# STM32_Schematic.net
KiCad netlist of a schematic drawn in Altium Designer
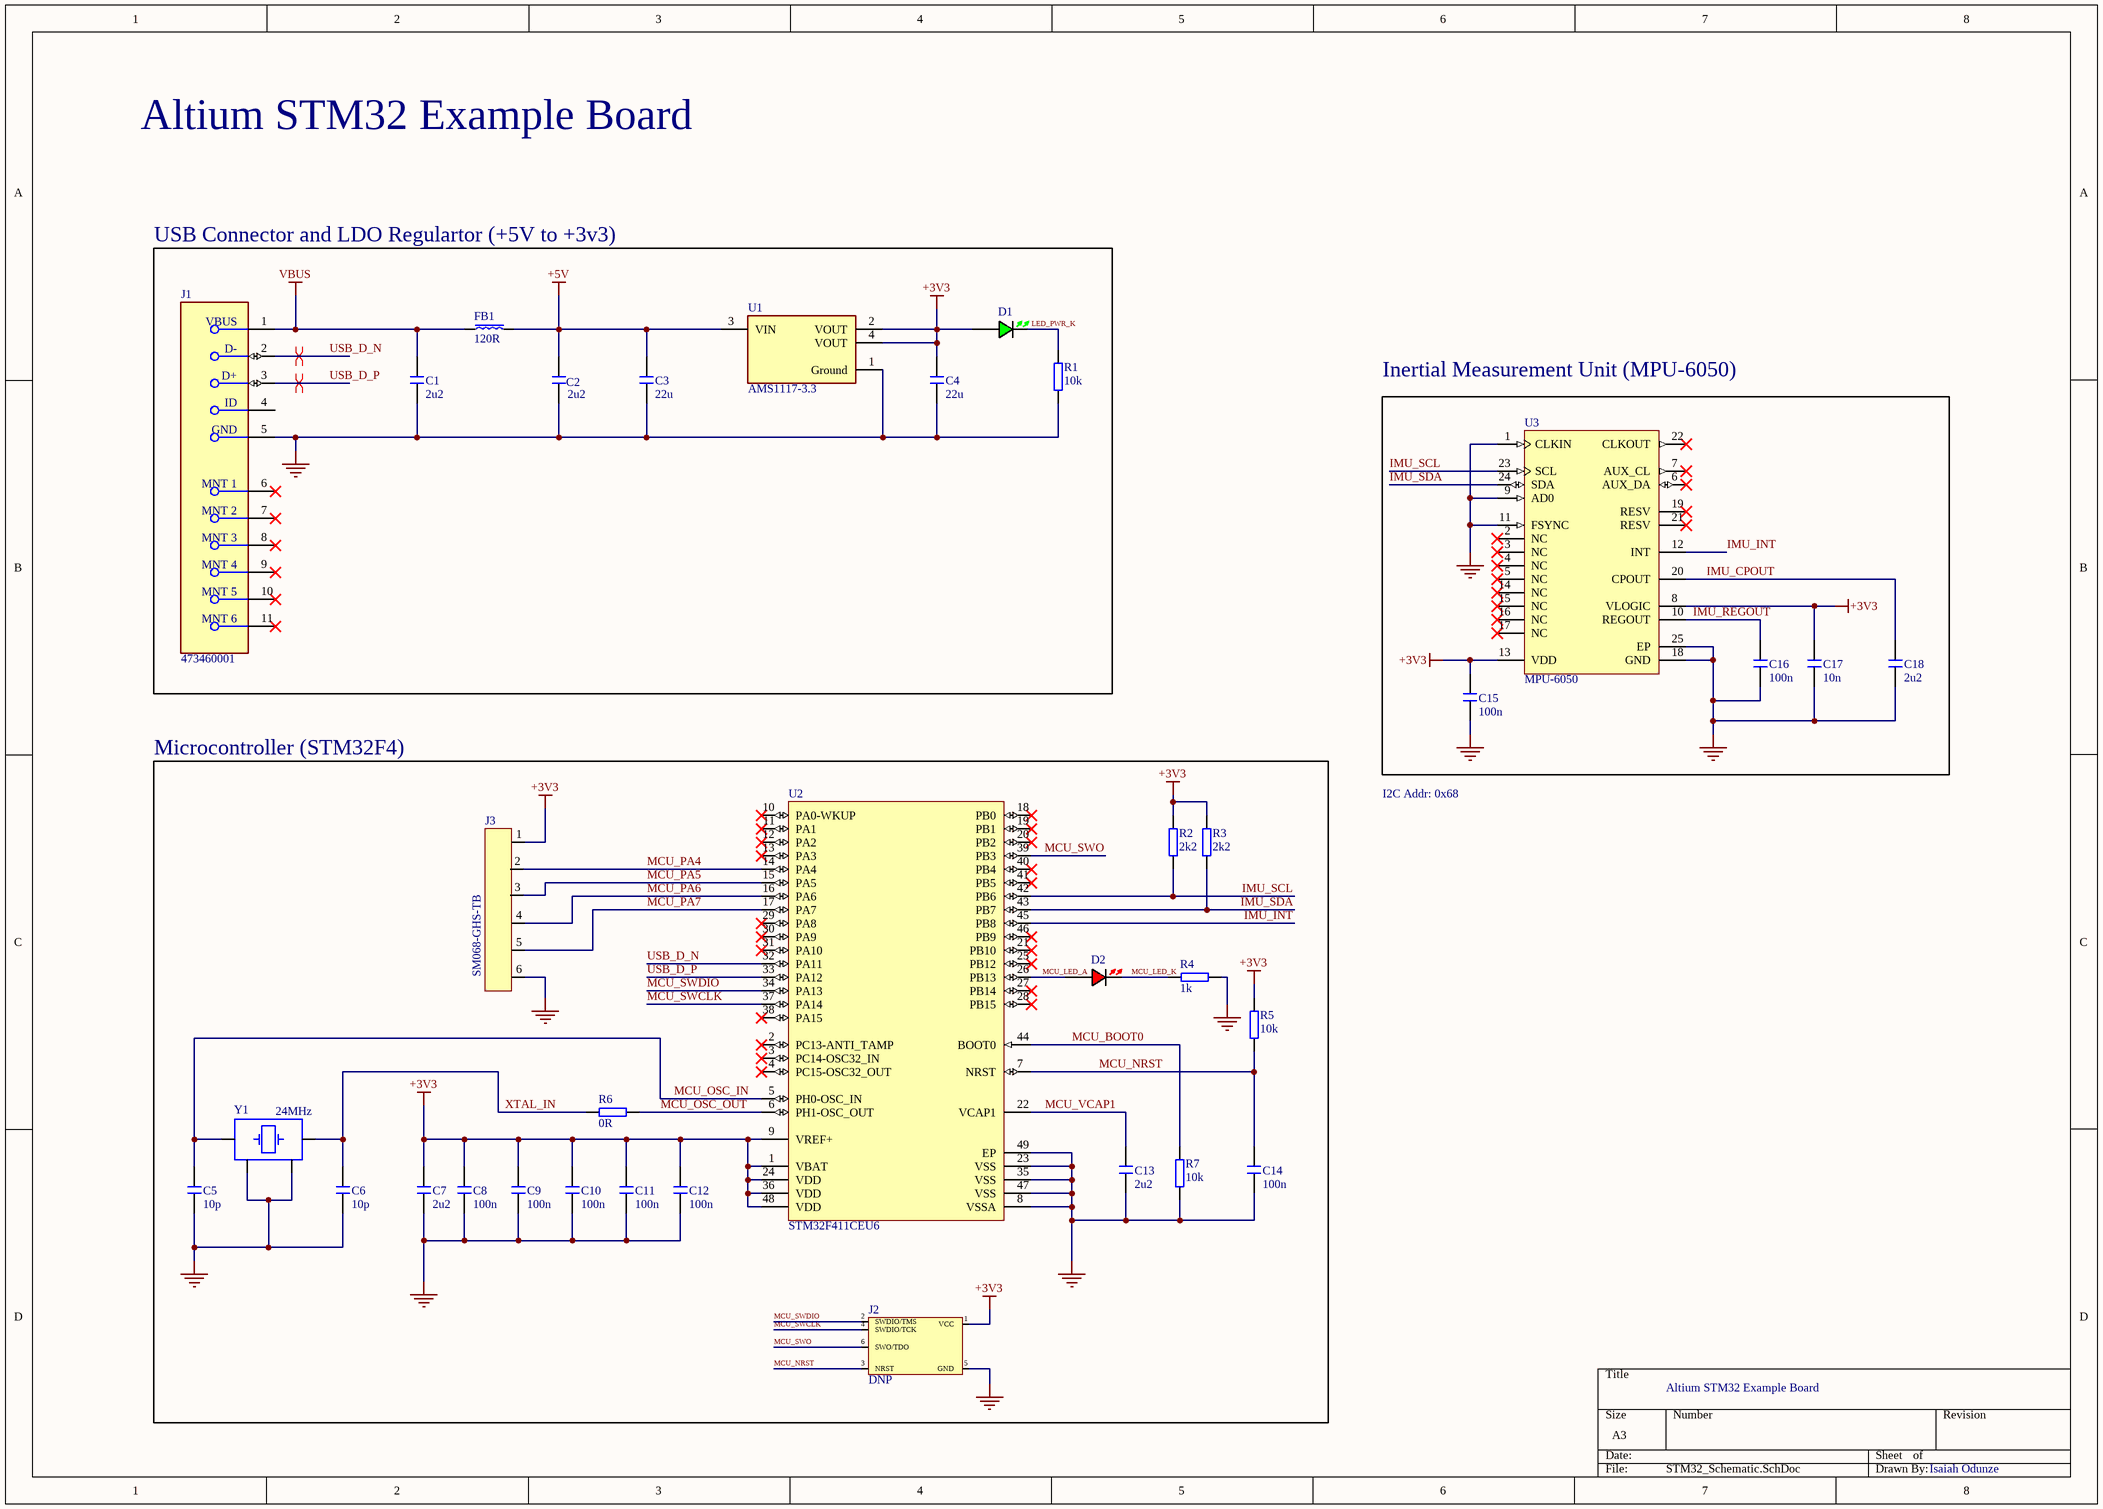
[diagram p0: STM32_Schematic.SchDoc]

(export (version "E")
  (design (tool "Eeschema 10.0.6"))
  (components
    (comp (ref "C1")
      (value "2u2")
      (footprint "CAP_0603_X_WAL")
      (libsource (lib "STM32F411CEU6") (part "CAP_0603_16V"))
    )
    (comp (ref "C2")
      (value "2u2")
      (footprint "CAP_0603_X_WAL")
      (libsource (lib "STM32F411CEU6") (part "CAP_0603_16V"))
    )
    (comp (ref "C3")
      (value "22u")
      (footprint "C0805")
      (description "CAP_SMD 0805 16V")
      (libsource (lib "STM32F411CEU6") (part "CAP_0805_16V"))
    )
    (comp (ref "C4")
      (value "22u")
      (footprint "C0805")
      (description "CAP_SMD 0805 16V")
      (libsource (lib "STM32F411CEU6") (part "CAP_0805_16V"))
    )
    (comp (ref "C5")
      (value "10p")
      (footprint "CAP_CL_05_SAM_0402")
      (description "0402 50V 10PF")
      (libsource (lib "STM32F411CEU6") (part "CAP_0402_50V"))
    )
    (comp (ref "C6")
      (value "10p")
      (footprint "CAP_CL_05_SAM_0402")
      (description "0402 50V 10PF")
      (libsource (lib "STM32F411CEU6") (part "CAP_0402_50V"))
    )
    (comp (ref "C7")
      (value "2u2")
      (footprint "CAP_0603_X_WAL")
      (libsource (lib "STM32F411CEU6") (part "CAP_0603_16V"))
    )
    (comp (ref "C8")
      (value "100n")
      (footprint "CAP_CL_05_SAM_0402")
      (libsource (lib "STM32F411CEU6") (part "CAP_0402_16V"))
    )
    (comp (ref "C9")
      (value "100n")
      (footprint "CAP_CL_05_SAM_0402")
      (libsource (lib "STM32F411CEU6") (part "CAP_0402_16V"))
    )
    (comp (ref "C10")
      (value "100n")
      (footprint "CAP_CL_05_SAM_0402")
      (libsource (lib "STM32F411CEU6") (part "CAP_0402_16V"))
    )
    (comp (ref "C11")
      (value "100n")
      (footprint "CAP_CL_05_SAM_0402")
      (libsource (lib "STM32F411CEU6") (part "CAP_0402_16V"))
    )
    (comp (ref "C12")
      (value "100n")
      (footprint "CAP_CL_05_SAM_0402")
      (libsource (lib "STM32F411CEU6") (part "CAP_0402_16V"))
    )
    (comp (ref "C13")
      (value "2u2")
      (footprint "CAP_0603_X_WAL")
      (libsource (lib "STM32F411CEU6") (part "CAP_0603_16V"))
    )
    (comp (ref "C14")
      (value "100n")
      (footprint "CAP_CL_05_SAM_0402")
      (libsource (lib "STM32F411CEU6") (part "CAP_0402_16V"))
    )
    (comp (ref "C15")
      (value "100n")
      (footprint "CAP_CL_05_SAM_0402")
      (libsource (lib "STM32F411CEU6") (part "CAP_0402_16V"))
    )
    (comp (ref "C16")
      (value "100n")
      (footprint "CAP_CL_05_SAM_0402")
      (libsource (lib "STM32F411CEU6") (part "CAP_0402_16V"))
    )
    (comp (ref "C17")
      (value "10n")
      (footprint "CAP_CL_05_SAM_0402")
      (libsource (lib "STM32F411CEU6") (part "CAP_0402_16V"))
    )
    (comp (ref "C18")
      (value "2u2")
      (footprint "CAP_0603_X_WAL")
      (libsource (lib "STM32F411CEU6") (part "CAP_0603_16V"))
    )
    (comp (ref "D1")
      (value "LED-0403-LED")
      (footprint "D0402")
      (description "LED-0402 green smd")
      (libsource (lib "STM32F411CEU6") (part "LED-0403-LED"))
    )
    (comp (ref "D2")
      (value "LED-0402-RED")
      (footprint "D0402")
      (description "LED-0402 red smd")
      (libsource (lib "STM32F411CEU6") (part "LED-0402-RED"))
    )
    (comp (ref "FB1")
      (value "120R")
      (footprint "IND_BLM18_0603_MUR-L")
      (description "Ferrite Beead SMD 0603")
      (libsource (lib "STM32F411CEU6") (part "FB_0603"))
    )
    (comp (ref "J1")
      (value "473460001")
      (footprint "FP-473460001-MFG")
      (description "CONN RCPT USB2.0 MICRO B SMD R/A")
      (fields
        (field (name "OCTOPART") "https://octopart.com/47346-0001-molex-7164928")
        (field (name "MANUFACTURER") "Molex")
      )
      (libsource (lib "Altium Content Vault") (part "53ae1f1d9b557310b43ca686e5bb76a"))
    )
    (comp (ref "J2")
      (value "DNP")
      (footprint "TAG_TC2030-IDC-NL")
      (description "TC2030-NL smd")
      (libsource (lib "STM32F411CEU6") (part "TC2030-NL"))
    )
    (comp (ref "J3")
      (value "SM068-GHS-TB")
      (footprint "CONN_SM06B-GHS-TB_JST")
      (libsource (lib "STM32F411CEU6") (part "SM068-GHS-TB"))
    )
    (comp (ref "R1") (value "10k") (footprint "R0402") (libsource (lib "STM32F411CEU6") (part "RES_0402")))
    (comp (ref "R2") (value "2k2") (footprint "R0402") (libsource (lib "STM32F411CEU6") (part "RES_0402")))
    (comp (ref "R3") (value "2k2") (footprint "R0402") (libsource (lib "STM32F411CEU6") (part "RES_0402")))
    (comp (ref "R4") (value "1k") (footprint "R0402") (libsource (lib "STM32F411CEU6") (part "RES_0402")))
    (comp (ref "R5") (value "10k") (footprint "R0402") (libsource (lib "STM32F411CEU6") (part "RES_0402")))
    (comp (ref "R6") (value "0R") (footprint "R0402") (libsource (lib "STM32F411CEU6") (part "RES_0402")))
    (comp (ref "R7") (value "10k") (footprint "R0402") (libsource (lib "STM32F411CEU6") (part "RES_0402")))
    (comp (ref "U1")
      (value "AMS1117-3.3")
      (footprint "FP-AMS1117-IPC_C")
      (description "LDO Voltage Regulators 1A, 3.3V")
      (fields
        (field (name "OCTOPART") "https://octopart.com/ams1117-3.3-advanced+monolithic+systems-25899300")
        (field (name "MANUFACTURER") "Advanced Monolithic Systems")
      )
      (libsource (lib "Altium Content Vault") (part "8bdbb5f8e77002000e30dd2845d0354"))
    )
    (comp (ref "U2")
      (value "STM32F411CEU6")
      (footprint "STM-UFQFPN48_L")
      (libsource (lib "Altium Content Vault") (part "MC-ARM-STM32F411-UFQFPN48"))
    )
    (comp (ref "U3")
      (value "MPU-6050")
      (footprint "IS-QFN-24_V")
      (fields (field (name "MANUFACTURER") "InvenSense"))
      (libsource (lib "Altium Content Vault") (part "IS-MPU-6050-QFN-24"))
    )
    (comp (ref "Y1")
      (value "24MHz")
      (footprint "TSX-3225 24.0000MF20G-AC3_EPS-L")
      (libsource (lib "STM32F411CEU6") (part "TSX-3225_24.0000MF20G_AC3"))
    )
  )
  (nets
    (net (code "1") (name "+3V3") (class "Default")
      (node (ref "C10") (pin "2") (pinfunction "2_2") (pintype "passive"))
      (node (ref "C11") (pin "2") (pinfunction "2_2") (pintype "passive"))
      (node (ref "C12") (pin "2") (pinfunction "2_2") (pintype "passive"))
      (node (ref "C15") (pin "2") (pinfunction "2_2") (pintype "passive"))
      (node (ref "C17") (pin "2") (pinfunction "2_2") (pintype "passive"))
      (node (ref "C4") (pin "2") (pinfunction "2_2") (pintype "passive"))
      (node (ref "C7") (pin "2") (pinfunction "2_2") (pintype "passive"))
      (node (ref "C8") (pin "2") (pinfunction "2_2") (pintype "passive"))
      (node (ref "C9") (pin "2") (pinfunction "2_2") (pintype "passive"))
      (node (ref "D1") (pin "A") (pinfunction "A_A") (pintype "passive"))
      (node (ref "J2") (pin "1") (pinfunction "VCC_1") (pintype "passive"))
      (node (ref "J3") (pin "1") (pinfunction "1_1") (pintype "passive"))
      (node (ref "R2") (pin "2") (pinfunction "2_2") (pintype "passive"))
      (node (ref "R3") (pin "2") (pinfunction "2_2") (pintype "passive"))
      (node (ref "R5") (pin "2") (pinfunction "2_2") (pintype "passive"))
      (node (ref "U1") (pin "2") (pinfunction "VOUT_2") (pintype "passive"))
      (node (ref "U1") (pin "4") (pinfunction "VOUT_4") (pintype "passive"))
      (node (ref "U2") (pin "1") (pinfunction "VBAT_1") (pintype "power_in"))
      (node (ref "U2") (pin "24") (pinfunction "VDD_24") (pintype "power_in"))
      (node (ref "U2") (pin "36") (pinfunction "VDD_36") (pintype "power_in"))
      (node (ref "U2") (pin "48") (pinfunction "VDD_48") (pintype "power_in"))
      (node (ref "U2") (pin "9") (pinfunction "VREF+_9") (pintype "power_in"))
      (node (ref "U3") (pin "13") (pinfunction "VDD_13") (pintype "power_in"))
      (node (ref "U3") (pin "8") (pinfunction "VLOGIC_8") (pintype "power_in"))
    )
    (net (code "2") (name "+5V") (class "Default")
      (node (ref "C2") (pin "2") (pinfunction "2_2") (pintype "passive"))
      (node (ref "C3") (pin "2") (pinfunction "2_2") (pintype "passive"))
      (node (ref "FB1") (pin "2") (pinfunction "2_2") (pintype "passive"))
      (node (ref "U1") (pin "3") (pinfunction "VIN_3") (pintype "power_in"))
    )
    (net (code "3") (name "/IMU_CPOUT") (class "Default")
      (node (ref "C18") (pin "2") (pinfunction "2_2") (pintype "passive"))
      (node (ref "U3") (pin "20") (pinfunction "CPOUT_20") (pintype "passive"))
    )
    (net (code "4") (name "/IMU_INT") (class "Default")
      (node (ref "U2") (pin "45") (pinfunction "PB8_45") (pintype "bidirectional"))
      (node (ref "U3") (pin "12") (pinfunction "INT_12") (pintype "open_collector"))
    )
    (net (code "5") (name "/IMU_REGOUT") (class "Default")
      (node (ref "C16") (pin "2") (pinfunction "2_2") (pintype "passive"))
      (node (ref "U3") (pin "10") (pinfunction "REGOUT_10") (pintype "passive"))
    )
    (net (code "6") (name "/IMU_SCL") (class "Default")
      (node (ref "R2") (pin "1") (pinfunction "1_1") (pintype "passive"))
      (node (ref "U2") (pin "42") (pinfunction "PB6_42") (pintype "bidirectional"))
      (node (ref "U3") (pin "23") (pinfunction "SCL_23") (pintype "input"))
    )
    (net (code "7") (name "/IMU_SDA") (class "Default")
      (node (ref "R3") (pin "1") (pinfunction "1_1") (pintype "passive"))
      (node (ref "U2") (pin "43") (pinfunction "PB7_43") (pintype "bidirectional"))
      (node (ref "U3") (pin "24") (pinfunction "SDA_24") (pintype "bidirectional"))
    )
    (net (code "8") (name "/LED_PWR_K") (class "Default")
      (node (ref "D1") (pin "K") (pinfunction "K_K") (pintype "passive"))
      (node (ref "R1") (pin "2") (pinfunction "2_2") (pintype "passive"))
    )
    (net (code "9") (name "/MCU_BOOT0") (class "Default")
      (node (ref "R7") (pin "2") (pinfunction "2_2") (pintype "passive"))
      (node (ref "U2") (pin "44") (pinfunction "BOOT0_44") (pintype "input"))
    )
    (net (code "10") (name "/MCU_LED_A") (class "Default")
      (node (ref "D2") (pin "A") (pinfunction "A_A") (pintype "passive"))
      (node (ref "U2") (pin "26") (pinfunction "PB13_26") (pintype "bidirectional"))
    )
    (net (code "11") (name "/MCU_LED_K") (class "Default")
      (node (ref "D2") (pin "K") (pinfunction "2_K") (pintype "passive"))
      (node (ref "R4") (pin "2") (pinfunction "2_2") (pintype "passive"))
    )
    (net (code "12") (name "/MCU_NRST") (class "Default")
      (node (ref "C14") (pin "2") (pinfunction "2_2") (pintype "passive"))
      (node (ref "J2") (pin "3") (pinfunction "NRST_3") (pintype "passive"))
      (node (ref "R5") (pin "1") (pinfunction "1_1") (pintype "passive"))
      (node (ref "U2") (pin "7") (pinfunction "NRST_7") (pintype "bidirectional"))
    )
    (net (code "13") (name "/MCU_OSC_IN") (class "Default")
      (node (ref "C5") (pin "2") (pinfunction "2_2") (pintype "passive"))
      (node (ref "U2") (pin "5") (pinfunction "PH0-OSC_IN_5") (pintype "bidirectional"))
      (node (ref "Y1") (pin "1") (pinfunction "1_1") (pintype "passive"))
    )
    (net (code "14") (name "/MCU_OSC_OUT") (class "Default")
      (node (ref "R6") (pin "2") (pinfunction "2_2") (pintype "passive"))
      (node (ref "U2") (pin "6") (pinfunction "PH1-OSC_OUT_6") (pintype "bidirectional"))
    )
    (net (code "15") (name "/MCU_PA4") (class "Default")
      (node (ref "J3") (pin "2") (pinfunction "2_2") (pintype "passive"))
      (node (ref "U2") (pin "14") (pinfunction "PA4_14") (pintype "bidirectional"))
    )
    (net (code "16") (name "/MCU_PA5") (class "Default")
      (node (ref "J3") (pin "3") (pinfunction "3_3") (pintype "passive"))
      (node (ref "U2") (pin "15") (pinfunction "PA5_15") (pintype "bidirectional"))
    )
    (net (code "17") (name "/MCU_PA6") (class "Default")
      (node (ref "J3") (pin "4") (pinfunction "4_4") (pintype "passive"))
      (node (ref "U2") (pin "16") (pinfunction "PA6_16") (pintype "bidirectional"))
    )
    (net (code "18") (name "/MCU_PA7") (class "Default")
      (node (ref "J3") (pin "5") (pinfunction "5_5") (pintype "passive"))
      (node (ref "U2") (pin "17") (pinfunction "PA7_17") (pintype "bidirectional"))
    )
    (net (code "19") (name "/MCU_SWCLK") (class "Default")
      (node (ref "J2") (pin "4") (pinfunction "SWDIO/TCK_4") (pintype "passive"))
      (node (ref "U2") (pin "37") (pinfunction "PA14_37") (pintype "bidirectional"))
    )
    (net (code "20") (name "/MCU_SWDIO") (class "Default")
      (node (ref "J2") (pin "2") (pinfunction "SWDIO/TMS_2") (pintype "passive"))
      (node (ref "U2") (pin "34") (pinfunction "PA13_34") (pintype "bidirectional"))
    )
    (net (code "21") (name "/MCU_SWO") (class "Default")
      (node (ref "J2") (pin "6") (pinfunction "SWO/TDO_6") (pintype "passive"))
      (node (ref "U2") (pin "39") (pinfunction "PB3_39") (pintype "bidirectional"))
    )
    (net (code "22") (name "/MCU_VCAP1") (class "Default")
      (node (ref "C13") (pin "2") (pinfunction "2_2") (pintype "passive"))
      (node (ref "U2") (pin "22") (pinfunction "VCAP1_22") (pintype "passive"))
    )
    (net (code "23") (name "/USB_D_N") (class "Default")
      (node (ref "J1") (pin "2") (pinfunction "D-_2") (pintype "bidirectional"))
      (node (ref "U2") (pin "32") (pinfunction "PA11_32") (pintype "bidirectional"))
    )
    (net (code "24") (name "/USB_D_P") (class "Default")
      (node (ref "J1") (pin "3") (pinfunction "D+_3") (pintype "bidirectional"))
      (node (ref "U2") (pin "33") (pinfunction "PA12_33") (pintype "bidirectional"))
    )
    (net (code "25") (name "/XTAL_IN") (class "Default")
      (node (ref "C6") (pin "2") (pinfunction "2_2") (pintype "passive"))
      (node (ref "R6") (pin "1") (pinfunction "1_1") (pintype "passive"))
      (node (ref "Y1") (pin "4") (pinfunction "4_4") (pintype "passive"))
    )
    (net (code "26") (name "GND") (class "Default")
      (node (ref "C1") (pin "1") (pinfunction "1_1") (pintype "passive"))
      (node (ref "C10") (pin "1") (pinfunction "1_1") (pintype "passive"))
      (node (ref "C11") (pin "1") (pinfunction "1_1") (pintype "passive"))
      (node (ref "C12") (pin "1") (pinfunction "1_1") (pintype "passive"))
      (node (ref "C13") (pin "1") (pinfunction "1_1") (pintype "passive"))
      (node (ref "C14") (pin "1") (pinfunction "1_1") (pintype "passive"))
      (node (ref "C15") (pin "1") (pinfunction "1_1") (pintype "passive"))
      (node (ref "C16") (pin "1") (pinfunction "1_1") (pintype "passive"))
      (node (ref "C17") (pin "1") (pinfunction "1_1") (pintype "passive"))
      (node (ref "C18") (pin "1") (pinfunction "1_1") (pintype "passive"))
      (node (ref "C2") (pin "1") (pinfunction "1_1") (pintype "passive"))
      (node (ref "C3") (pin "1") (pinfunction "1_1") (pintype "passive"))
      (node (ref "C4") (pin "1") (pinfunction "1_1") (pintype "passive"))
      (node (ref "C5") (pin "1") (pinfunction "1_1") (pintype "passive"))
      (node (ref "C6") (pin "1") (pinfunction "1_1") (pintype "passive"))
      (node (ref "C7") (pin "1") (pinfunction "1_1") (pintype "passive"))
      (node (ref "C8") (pin "1") (pinfunction "1_1") (pintype "passive"))
      (node (ref "C9") (pin "1") (pinfunction "1_1") (pintype "passive"))
      (node (ref "J1") (pin "5") (pinfunction "GND_5") (pintype "power_in"))
      (node (ref "J2") (pin "5") (pinfunction "GND_5") (pintype "passive"))
      (node (ref "J3") (pin "6") (pinfunction "6_6") (pintype "passive"))
      (node (ref "R1") (pin "1") (pinfunction "1_1") (pintype "passive"))
      (node (ref "R4") (pin "1") (pinfunction "1_1") (pintype "passive"))
      (node (ref "R7") (pin "1") (pinfunction "1_1") (pintype "passive"))
      (node (ref "U1") (pin "1") (pinfunction "Ground_1") (pintype "power_in"))
      (node (ref "U2") (pin "23") (pinfunction "VSS_23") (pintype "power_in"))
      (node (ref "U2") (pin "35") (pinfunction "VSS_35") (pintype "power_in"))
      (node (ref "U2") (pin "47") (pinfunction "VSS_47") (pintype "power_in"))
      (node (ref "U2") (pin "49") (pinfunction "EP_49") (pintype "power_in"))
      (node (ref "U2") (pin "8") (pinfunction "VSSA_8") (pintype "power_in"))
      (node (ref "U3") (pin "1") (pinfunction "CLKIN_1") (pintype "input"))
      (node (ref "U3") (pin "11") (pinfunction "FSYNC_11") (pintype "input"))
      (node (ref "U3") (pin "18") (pinfunction "GND_18") (pintype "power_in"))
      (node (ref "U3") (pin "25") (pinfunction "EP_25") (pintype "power_in"))
      (node (ref "U3") (pin "9") (pinfunction "AD0_9") (pintype "input"))
      (node (ref "Y1") (pin "2") (pinfunction "2_2") (pintype "passive"))
      (node (ref "Y1") (pin "3") (pinfunction "3_3") (pintype "passive"))
    )
    (net (code "27") (name "VBUS") (class "Default")
      (node (ref "C1") (pin "2") (pinfunction "2_2") (pintype "passive"))
      (node (ref "FB1") (pin "1") (pinfunction "1_1") (pintype "passive"))
      (node (ref "J1") (pin "1") (pinfunction "VBUS_1") (pintype "power_in"))
    )
    (net (code "28") (name "unconnected-(J1-ID-Pad4)") (class "Default")
      (node (ref "J1") (pin "4") (pinfunction "ID_4") (pintype "passive"))
    )
    (net (code "29") (name "unconnected-(J1-MNT_1-Pad6)") (class "Default")
      (node (ref "J1") (pin "6") (pinfunction "MNT_1_6") (pintype "passive+no_connect"))
    )
    (net (code "30") (name "unconnected-(J1-MNT_2-Pad7)") (class "Default")
      (node (ref "J1") (pin "7") (pinfunction "MNT_2_7") (pintype "passive+no_connect"))
    )
    (net (code "31") (name "unconnected-(J1-MNT_3-Pad8)") (class "Default")
      (node (ref "J1") (pin "8") (pinfunction "MNT_3_8") (pintype "passive+no_connect"))
    )
    (net (code "32") (name "unconnected-(J1-MNT_4-Pad9)") (class "Default")
      (node (ref "J1") (pin "9") (pinfunction "MNT_4_9") (pintype "passive+no_connect"))
    )
    (net (code "33") (name "unconnected-(J1-MNT_5-Pad10)") (class "Default")
      (node (ref "J1") (pin "10") (pinfunction "MNT_5_10") (pintype "passive+no_connect"))
    )
    (net (code "34") (name "unconnected-(J1-MNT_6-Pad11)") (class "Default")
      (node (ref "J1") (pin "11") (pinfunction "MNT_6_11") (pintype "passive+no_connect"))
    )
    (net (code "35") (name "unconnected-(U2-PA0-WKUP-Pad10)") (class "Default")
      (node (ref "U2") (pin "10") (pinfunction "PA0-WKUP_10") (pintype "bidirectional+no_connect"))
    )
    (net (code "36") (name "unconnected-(U2-PA1-Pad11)") (class "Default")
      (node (ref "U2") (pin "11") (pinfunction "PA1_11") (pintype "bidirectional+no_connect"))
    )
    (net (code "37") (name "unconnected-(U2-PA2-Pad12)") (class "Default")
      (node (ref "U2") (pin "12") (pinfunction "PA2_12") (pintype "bidirectional+no_connect"))
    )
    (net (code "38") (name "unconnected-(U2-PA3-Pad13)") (class "Default")
      (node (ref "U2") (pin "13") (pinfunction "PA3_13") (pintype "bidirectional+no_connect"))
    )
    (net (code "39") (name "unconnected-(U2-PA8-Pad29)") (class "Default")
      (node (ref "U2") (pin "29") (pinfunction "PA8_29") (pintype "bidirectional+no_connect"))
    )
    (net (code "40") (name "unconnected-(U2-PA9-Pad30)") (class "Default")
      (node (ref "U2") (pin "30") (pinfunction "PA9_30") (pintype "bidirectional+no_connect"))
    )
    (net (code "41") (name "unconnected-(U2-PA10-Pad31)") (class "Default")
      (node (ref "U2") (pin "31") (pinfunction "PA10_31") (pintype "bidirectional+no_connect"))
    )
    (net (code "42") (name "unconnected-(U2-PA15-Pad38)") (class "Default")
      (node (ref "U2") (pin "38") (pinfunction "PA15_38") (pintype "bidirectional+no_connect"))
    )
    (net (code "43") (name "unconnected-(U2-PB0-Pad18)") (class "Default")
      (node (ref "U2") (pin "18") (pinfunction "PB0_18") (pintype "bidirectional+no_connect"))
    )
    (net (code "44") (name "unconnected-(U2-PB1-Pad19)") (class "Default")
      (node (ref "U2") (pin "19") (pinfunction "PB1_19") (pintype "bidirectional+no_connect"))
    )
    (net (code "45") (name "unconnected-(U2-PB2-Pad20)") (class "Default")
      (node (ref "U2") (pin "20") (pinfunction "PB2_20") (pintype "bidirectional+no_connect"))
    )
    (net (code "46") (name "unconnected-(U2-PB4-Pad40)") (class "Default")
      (node (ref "U2") (pin "40") (pinfunction "PB4_40") (pintype "bidirectional+no_connect"))
    )
    (net (code "47") (name "unconnected-(U2-PB5-Pad41)") (class "Default")
      (node (ref "U2") (pin "41") (pinfunction "PB5_41") (pintype "bidirectional+no_connect"))
    )
    (net (code "48") (name "unconnected-(U2-PB9-Pad46)") (class "Default")
      (node (ref "U2") (pin "46") (pinfunction "PB9_46") (pintype "bidirectional+no_connect"))
    )
    (net (code "49") (name "unconnected-(U2-PB10-Pad21)") (class "Default")
      (node (ref "U2") (pin "21") (pinfunction "PB10_21") (pintype "bidirectional+no_connect"))
    )
    (net (code "50") (name "unconnected-(U2-PB12-Pad25)") (class "Default")
      (node (ref "U2") (pin "25") (pinfunction "PB12_25") (pintype "bidirectional+no_connect"))
    )
    (net (code "51") (name "unconnected-(U2-PB14-Pad27)") (class "Default")
      (node (ref "U2") (pin "27") (pinfunction "PB14_27") (pintype "bidirectional+no_connect"))
    )
    (net (code "52") (name "unconnected-(U2-PB15-Pad28)") (class "Default")
      (node (ref "U2") (pin "28") (pinfunction "PB15_28") (pintype "bidirectional+no_connect"))
    )
    (net (code "53") (name "unconnected-(U2-PC13-ANTI_TAMP-Pad2)") (class "Default")
      (node (ref "U2") (pin "2") (pinfunction "PC13-ANTI_TAMP_2") (pintype "bidirectional+no_connect"))
    )
    (net (code "54") (name "unconnected-(U2-PC14-OSC32_IN-Pad3)") (class "Default")
      (node (ref "U2") (pin "3") (pinfunction "PC14-OSC32_IN_3") (pintype "bidirectional+no_connect"))
    )
    (net (code "55") (name "unconnected-(U2-PC15-OSC32_OUT-Pad4)") (class "Default")
      (node (ref "U2") (pin "4") (pinfunction "PC15-OSC32_OUT_4") (pintype "bidirectional+no_connect"))
    )
    (net (code "56") (name "unconnected-(U3-AUX_CL-Pad7)") (class "Default")
      (node (ref "U3") (pin "7") (pinfunction "AUX_CL_7") (pintype "output+no_connect"))
    )
    (net (code "57") (name "unconnected-(U3-AUX_DA-Pad6)") (class "Default")
      (node (ref "U3") (pin "6") (pinfunction "AUX_DA_6") (pintype "bidirectional+no_connect"))
    )
    (net (code "58") (name "unconnected-(U3-CLKOUT-Pad22)") (class "Default")
      (node (ref "U3") (pin "22") (pinfunction "CLKOUT_22") (pintype "output+no_connect"))
    )
    (net (code "59") (name "unconnected-(U3-NC-Pad2)") (class "Default")
      (node (ref "U3") (pin "2") (pinfunction "NC_2") (pintype "passive+no_connect"))
    )
    (net (code "60") (name "unconnected-(U3-NC-Pad3)") (class "Default")
      (node (ref "U3") (pin "3") (pinfunction "NC_3") (pintype "passive+no_connect"))
    )
    (net (code "61") (name "unconnected-(U3-NC-Pad4)") (class "Default")
      (node (ref "U3") (pin "4") (pinfunction "NC_4") (pintype "passive+no_connect"))
    )
    (net (code "62") (name "unconnected-(U3-NC-Pad5)") (class "Default")
      (node (ref "U3") (pin "5") (pinfunction "NC_5") (pintype "passive+no_connect"))
    )
    (net (code "63") (name "unconnected-(U3-NC-Pad14)") (class "Default")
      (node (ref "U3") (pin "14") (pinfunction "NC_14") (pintype "passive+no_connect"))
    )
    (net (code "64") (name "unconnected-(U3-NC-Pad15)") (class "Default")
      (node (ref "U3") (pin "15") (pinfunction "NC_15") (pintype "passive+no_connect"))
    )
    (net (code "65") (name "unconnected-(U3-NC-Pad16)") (class "Default")
      (node (ref "U3") (pin "16") (pinfunction "NC_16") (pintype "passive+no_connect"))
    )
    (net (code "66") (name "unconnected-(U3-NC-Pad17)") (class "Default")
      (node (ref "U3") (pin "17") (pinfunction "NC_17") (pintype "passive+no_connect"))
    )
    (net (code "67") (name "unconnected-(U3-RESV-Pad19)") (class "Default")
      (node (ref "U3") (pin "19") (pinfunction "RESV_19") (pintype "passive+no_connect"))
    )
    (net (code "68") (name "unconnected-(U3-RESV-Pad21)") (class "Default")
      (node (ref "U3") (pin "21") (pinfunction "RESV_21") (pintype "passive+no_connect"))
    )
  )
)
